# crossingsignals.net
KiCad netlist of a schematic drawn in EAGLE
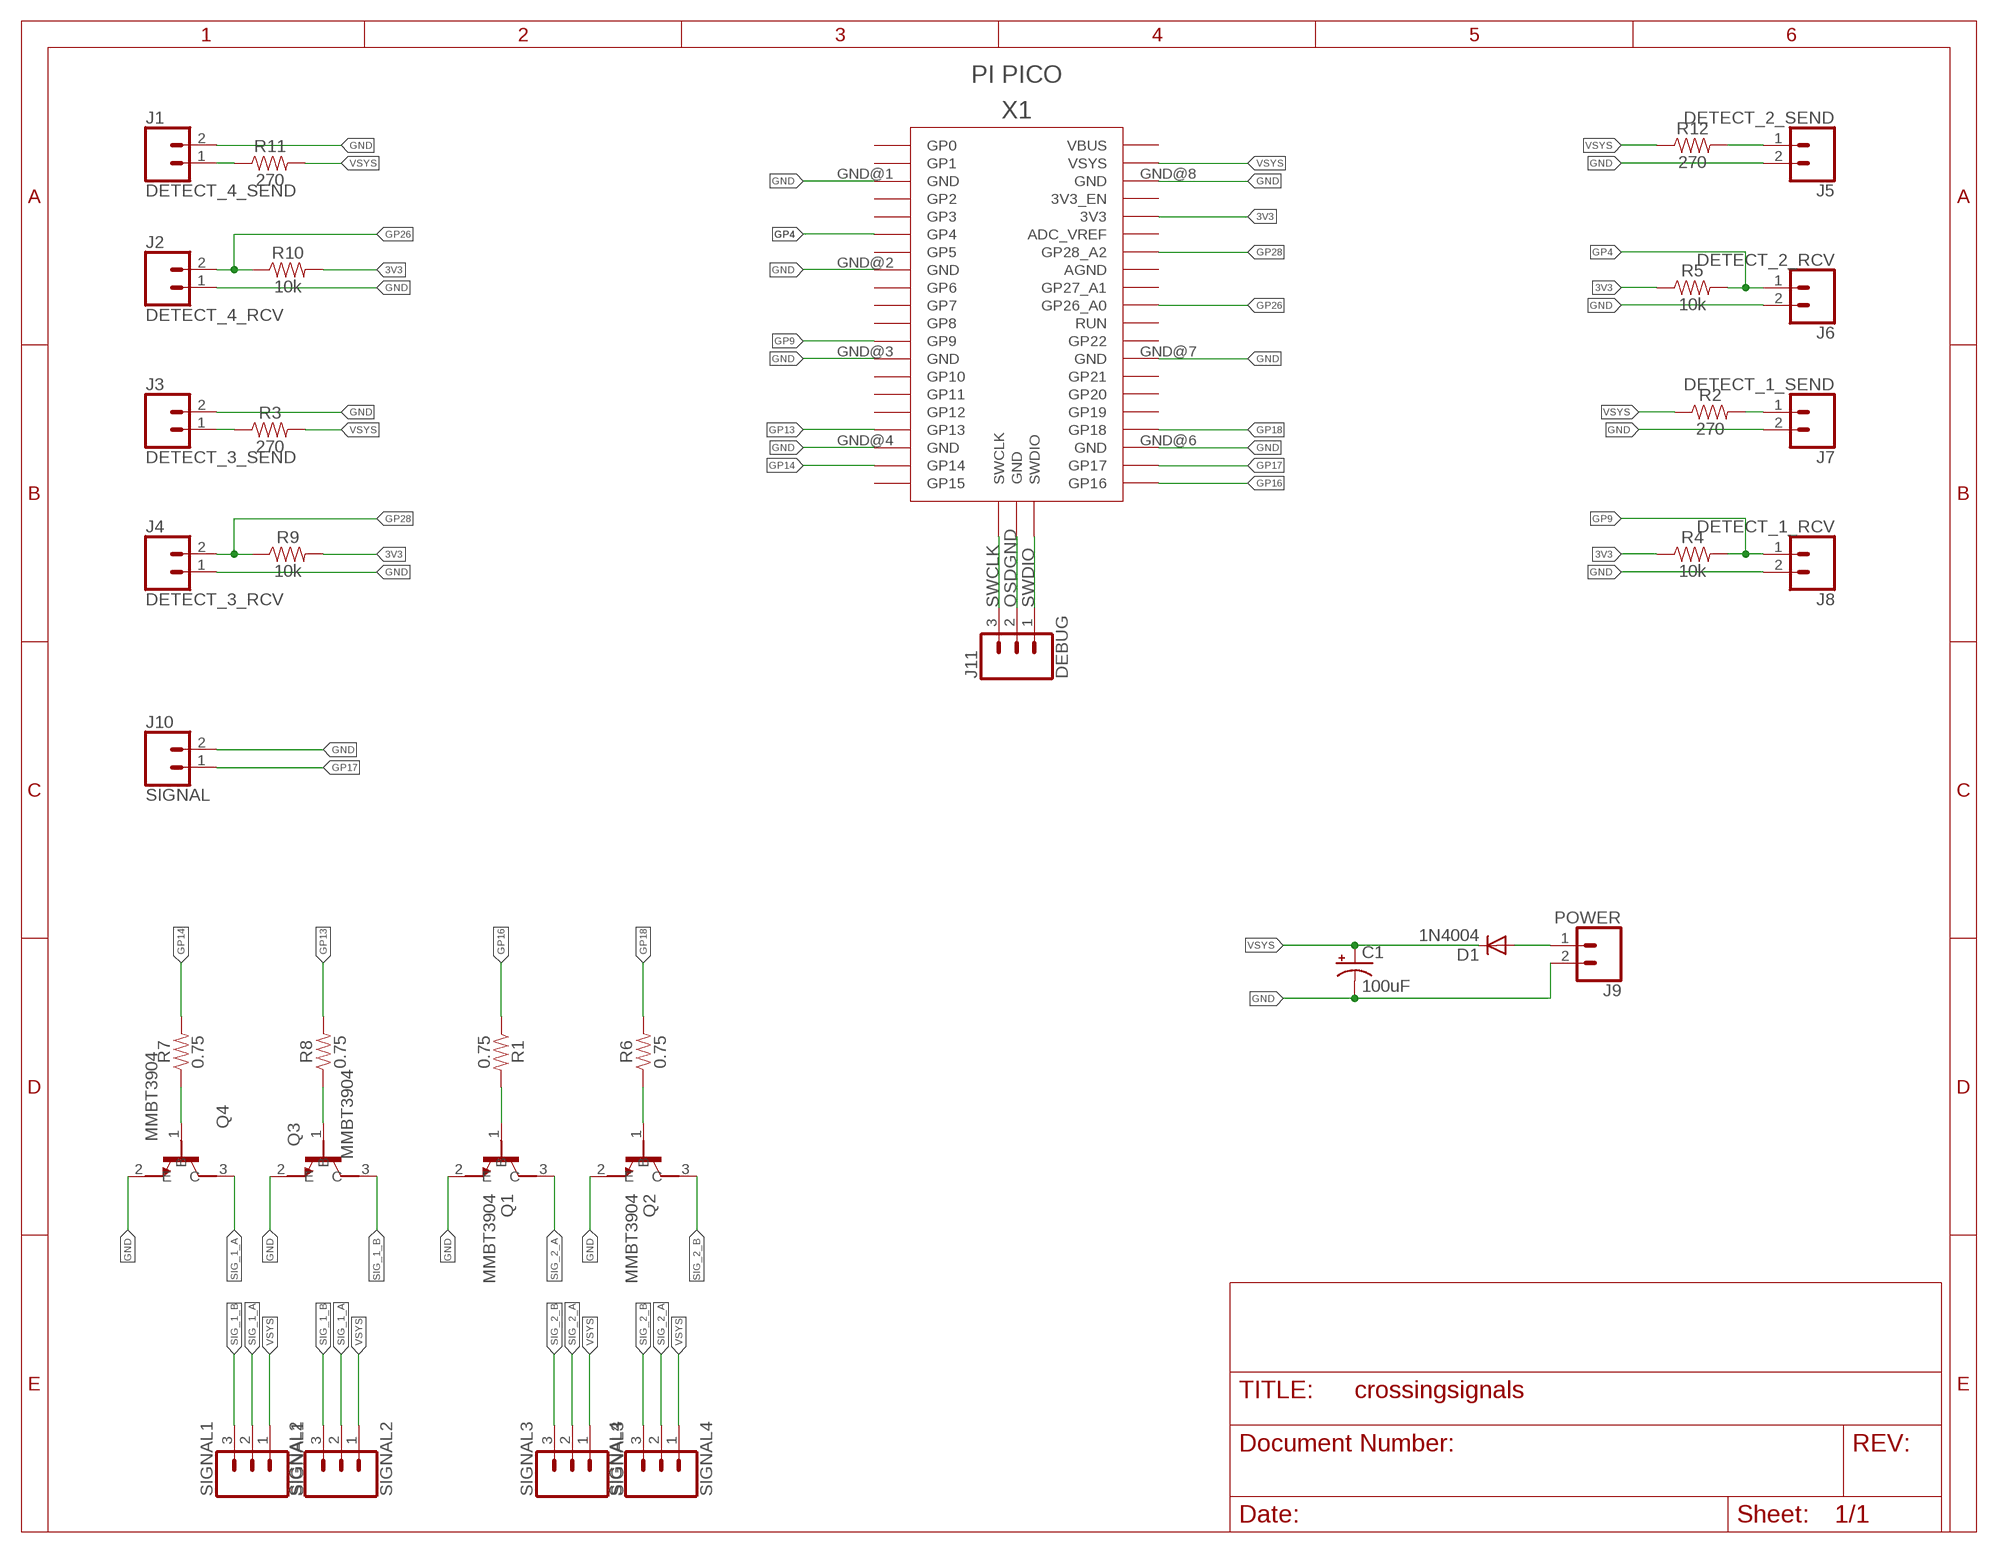
[diagram p0: schematic, sheet 1]

(export (version "E")
  (design (tool "Eeschema 10.0.6"))
  (components
    (comp (ref "C1")
      (value "100uF")
      (footprint "eagle-import:CPOL-RADIAL-2.5MM-6.5MM")
      (libsource (lib "eagle-import") (part "100UF-POLAR-RADIAL-2.5MM-25V-20%"))
    )
    (comp (ref "D1")
      (value "1N4004")
      (footprint "eagle-import:DO41-10")
      (libsource (lib "eagle-import") (part "1N4004"))
    )
    (comp (ref "J1")
      (value "DETECT_4_SEND")
      (footprint "eagle-import:1X02")
      (libsource (lib "eagle-import") (part "CONN_02"))
    )
    (comp (ref "J2")
      (value "DETECT_4_RCV")
      (footprint "eagle-import:1X02")
      (libsource (lib "eagle-import") (part "CONN_02"))
    )
    (comp (ref "J3")
      (value "DETECT_3_SEND")
      (footprint "eagle-import:1X02")
      (libsource (lib "eagle-import") (part "CONN_02"))
    )
    (comp (ref "J4")
      (value "DETECT_3_RCV")
      (footprint "eagle-import:1X02")
      (libsource (lib "eagle-import") (part "CONN_02"))
    )
    (comp (ref "J5")
      (value "DETECT_2_SEND")
      (footprint "eagle-import:1X02")
      (libsource (lib "eagle-import") (part "CONN_02"))
    )
    (comp (ref "J6")
      (value "DETECT_2_RCV")
      (footprint "eagle-import:1X02")
      (libsource (lib "eagle-import") (part "CONN_02"))
    )
    (comp (ref "J7")
      (value "DETECT_1_SEND")
      (footprint "eagle-import:1X02")
      (libsource (lib "eagle-import") (part "CONN_02"))
    )
    (comp (ref "J8")
      (value "DETECT_1_RCV")
      (footprint "eagle-import:1X02")
      (libsource (lib "eagle-import") (part "CONN_02"))
    )
    (comp (ref "J9")
      (value "POWER")
      (footprint "eagle-import:1X02")
      (libsource (lib "eagle-import") (part "CONN_02"))
    )
    (comp (ref "J10")
      (value "SIGNAL")
      (footprint "eagle-import:1X02")
      (libsource (lib "eagle-import") (part "CONN_02"))
    )
    (comp (ref "J11")
      (value "DEBUG")
      (footprint "eagle-import:1X03")
      (libsource (lib "eagle-import") (part "CONN_03"))
    )
    (comp (ref "Q1")
      (value "MMBT3904")
      (footprint "eagle-import:SOT95P240X120-3N")
      (fields (field (name "MF") "STMicroelectronics"))
      (libsource (lib "eagle-import") (part "MMBT3904"))
    )
    (comp (ref "Q2")
      (value "MMBT3904")
      (footprint "eagle-import:SOT95P240X120-3N")
      (fields (field (name "MF") "STMicroelectronics"))
      (libsource (lib "eagle-import") (part "MMBT3904"))
    )
    (comp (ref "Q3")
      (value "MMBT3904")
      (footprint "eagle-import:SOT95P240X120-3N")
      (fields (field (name "MF") "STMicroelectronics"))
      (libsource (lib "eagle-import") (part "MMBT3904"))
    )
    (comp (ref "Q4")
      (value "MMBT3904")
      (footprint "eagle-import:SOT95P240X120-3N")
      (fields (field (name "MF") "STMicroelectronics"))
      (libsource (lib "eagle-import") (part "MMBT3904"))
    )
    (comp (ref "R1")
      (value "0.75")
      (footprint "eagle-import:0805")
      (libsource (lib "eagle-import") (part "0.75OHM-0805-1/4W-1%"))
    )
    (comp (ref "R2")
      (value "270")
      (footprint "eagle-import:0805")
      (libsource (lib "eagle-import") (part "0.75OHM-0805-1/4W-1%"))
    )
    (comp (ref "R3")
      (value "270")
      (footprint "eagle-import:0805")
      (libsource (lib "eagle-import") (part "0.75OHM-0805-1/4W-1%"))
    )
    (comp (ref "R4")
      (value "10k")
      (footprint "eagle-import:0805")
      (libsource (lib "eagle-import") (part "0.75OHM-0805-1/4W-1%"))
    )
    (comp (ref "R5")
      (value "10k")
      (footprint "eagle-import:0805")
      (libsource (lib "eagle-import") (part "0.75OHM-0805-1/4W-1%"))
    )
    (comp (ref "R6")
      (value "0.75")
      (footprint "eagle-import:0805")
      (libsource (lib "eagle-import") (part "0.75OHM-0805-1/4W-1%"))
    )
    (comp (ref "R7")
      (value "0.75")
      (footprint "eagle-import:0805")
      (libsource (lib "eagle-import") (part "0.75OHM-0805-1/4W-1%"))
    )
    (comp (ref "R8")
      (value "0.75")
      (footprint "eagle-import:0805")
      (libsource (lib "eagle-import") (part "0.75OHM-0805-1/4W-1%"))
    )
    (comp (ref "R9")
      (value "10k")
      (footprint "eagle-import:0805")
      (libsource (lib "eagle-import") (part "0.75OHM-0805-1/4W-1%"))
    )
    (comp (ref "R10")
      (value "10k")
      (footprint "eagle-import:0805")
      (libsource (lib "eagle-import") (part "0.75OHM-0805-1/4W-1%"))
    )
    (comp (ref "R11")
      (value "270")
      (footprint "eagle-import:0805")
      (libsource (lib "eagle-import") (part "0.75OHM-0805-1/4W-1%"))
    )
    (comp (ref "R12")
      (value "270")
      (footprint "eagle-import:0805")
      (libsource (lib "eagle-import") (part "0.75OHM-0805-1/4W-1%"))
    )
    (comp (ref "SIGNAL1")
      (value "SIGNAL1")
      (footprint "eagle-import:1X03")
      (libsource (lib "eagle-import") (part "CONN_03"))
    )
    (comp (ref "SIGNAL2")
      (value "SIGNAL2")
      (footprint "eagle-import:1X03")
      (libsource (lib "eagle-import") (part "CONN_03"))
    )
    (comp (ref "SIGNAL3")
      (value "SIGNAL3")
      (footprint "eagle-import:1X03")
      (libsource (lib "eagle-import") (part "CONN_03"))
    )
    (comp (ref "SIGNAL4")
      (value "SIGNAL4")
      (footprint "eagle-import:1X03")
      (libsource (lib "eagle-import") (part "CONN_03"))
    )
    (comp (ref "X1")
      (value "PI PICO")
      (footprint "eagle-import:RPI_PICO_TH")
      (libsource (lib "eagle-import") (part "RPI_PICO_IG-TH"))
    )
  )
  (nets
    (net (code "1") (name "/OSDGND") (class "Default")
      (node (ref "J11") (pin "2") (pinfunction "2_2") (pintype "passive"))
      (node (ref "X1") (pin "GND@5") (pinfunction "GND_GND@5") (pintype "bidirectional"))
    )
    (net (code "2") (name "/SWCLK") (class "Default")
      (node (ref "J11") (pin "3") (pinfunction "3_3") (pintype "passive"))
      (node (ref "X1") (pin "SWCLK") (pinfunction "SWCLK_SWCLK") (pintype "bidirectional"))
    )
    (net (code "3") (name "/SWDIO") (class "Default")
      (node (ref "J11") (pin "1") (pinfunction "1_1") (pintype "passive"))
      (node (ref "X1") (pin "SWDIO") (pinfunction "SWDIO_SWDIO") (pintype "bidirectional"))
    )
    (net (code "4") (name "3V3") (class "Default")
      (node (ref "R10") (pin "2") (pinfunction "2_2") (pintype "passive"))
      (node (ref "R4") (pin "1") (pinfunction "1_1") (pintype "passive"))
      (node (ref "R5") (pin "1") (pinfunction "1_1") (pintype "passive"))
      (node (ref "R9") (pin "2") (pinfunction "2_2") (pintype "passive"))
      (node (ref "X1") (pin "3V3") (pinfunction "3V3_3V3") (pintype "bidirectional"))
    )
    (net (code "5") (name "GND") (class "Default")
      (node (ref "C1") (pin "2") (pinfunction "-_2") (pintype "passive"))
      (node (ref "J1") (pin "2") (pinfunction "2_2") (pintype "passive"))
      (node (ref "J10") (pin "2") (pinfunction "2_2") (pintype "passive"))
      (node (ref "J2") (pin "1") (pinfunction "1_1") (pintype "passive"))
      (node (ref "J3") (pin "2") (pinfunction "2_2") (pintype "passive"))
      (node (ref "J4") (pin "1") (pinfunction "1_1") (pintype "passive"))
      (node (ref "J5") (pin "2") (pinfunction "2_2") (pintype "passive"))
      (node (ref "J6") (pin "2") (pinfunction "2_2") (pintype "passive"))
      (node (ref "J7") (pin "2") (pinfunction "2_2") (pintype "passive"))
      (node (ref "J8") (pin "2") (pinfunction "2_2") (pintype "passive"))
      (node (ref "J9") (pin "2") (pinfunction "2_2") (pintype "passive"))
      (node (ref "Q1") (pin "2") (pinfunction "E_2") (pintype "passive"))
      (node (ref "Q2") (pin "2") (pinfunction "E_2") (pintype "passive"))
      (node (ref "Q3") (pin "2") (pinfunction "E_2") (pintype "passive"))
      (node (ref "Q4") (pin "2") (pinfunction "E_2") (pintype "passive"))
      (node (ref "X1") (pin "GND@1") (pinfunction "GND_GND@1") (pintype "bidirectional"))
      (node (ref "X1") (pin "GND@2") (pinfunction "GND_GND@2") (pintype "bidirectional"))
      (node (ref "X1") (pin "GND@3") (pinfunction "GND_GND@3") (pintype "bidirectional"))
      (node (ref "X1") (pin "GND@4") (pinfunction "GND_GND@4") (pintype "bidirectional"))
      (node (ref "X1") (pin "GND@6") (pinfunction "GND_GND@6") (pintype "bidirectional"))
      (node (ref "X1") (pin "GND@7") (pinfunction "GND_GND@7") (pintype "bidirectional"))
      (node (ref "X1") (pin "GND@8") (pinfunction "GND_GND@8") (pintype "bidirectional"))
    )
    (net (code "6") (name "GP4") (class "Default")
      (node (ref "J6") (pin "1") (pinfunction "1_1") (pintype "passive"))
      (node (ref "R5") (pin "2") (pinfunction "2_2") (pintype "passive"))
      (node (ref "X1") (pin "GP4") (pinfunction "GP4_GP4") (pintype "bidirectional"))
    )
    (net (code "7") (name "GP9") (class "Default")
      (node (ref "J8") (pin "1") (pinfunction "1_1") (pintype "passive"))
      (node (ref "R4") (pin "2") (pinfunction "2_2") (pintype "passive"))
      (node (ref "X1") (pin "GP9") (pinfunction "GP9_GP9") (pintype "bidirectional"))
    )
    (net (code "8") (name "GP13") (class "Default")
      (node (ref "R8") (pin "2") (pinfunction "2_2") (pintype "passive"))
      (node (ref "X1") (pin "GP13") (pinfunction "GP13_GP13") (pintype "bidirectional"))
    )
    (net (code "9") (name "GP14") (class "Default")
      (node (ref "R7") (pin "2") (pinfunction "2_2") (pintype "passive"))
      (node (ref "X1") (pin "GP14") (pinfunction "GP14_GP14") (pintype "bidirectional"))
    )
    (net (code "10") (name "GP16") (class "Default")
      (node (ref "R1") (pin "1") (pinfunction "1_1") (pintype "passive"))
      (node (ref "X1") (pin "GP16") (pinfunction "GP16_GP16") (pintype "bidirectional"))
    )
    (net (code "11") (name "GP17") (class "Default")
      (node (ref "J10") (pin "1") (pinfunction "1_1") (pintype "passive"))
      (node (ref "X1") (pin "GP17") (pinfunction "GP17_GP17") (pintype "bidirectional"))
    )
    (net (code "12") (name "GP18") (class "Default")
      (node (ref "R6") (pin "2") (pinfunction "2_2") (pintype "passive"))
      (node (ref "X1") (pin "GP18") (pinfunction "GP18_GP18") (pintype "bidirectional"))
    )
    (net (code "13") (name "GP26") (class "Default")
      (node (ref "J2") (pin "2") (pinfunction "2_2") (pintype "passive"))
      (node (ref "R10") (pin "1") (pinfunction "1_1") (pintype "passive"))
      (node (ref "X1") (pin "GP26_A0") (pinfunction "GP26_A0_GP26_A0") (pintype "bidirectional"))
    )
    (net (code "14") (name "GP28") (class "Default")
      (node (ref "J4") (pin "2") (pinfunction "2_2") (pintype "passive"))
      (node (ref "R9") (pin "1") (pinfunction "1_1") (pintype "passive"))
      (node (ref "X1") (pin "GP28_A2") (pinfunction "GP28_A2_GP28_A2") (pintype "bidirectional"))
    )
    (net (code "15") (name "Net-(D1-PadA)") (class "Default")
      (node (ref "D1") (pin "A") (pinfunction "A_A") (pintype "passive"))
      (node (ref "J9") (pin "1") (pinfunction "1_1") (pintype "passive"))
    )
    (net (code "16") (name "Net-(J1-Pad1)") (class "Default")
      (node (ref "J1") (pin "1") (pinfunction "1_1") (pintype "passive"))
      (node (ref "R11") (pin "1") (pinfunction "1_1") (pintype "passive"))
    )
    (net (code "17") (name "Net-(J3-Pad1)") (class "Default")
      (node (ref "J3") (pin "1") (pinfunction "1_1") (pintype "passive"))
      (node (ref "R3") (pin "1") (pinfunction "1_1") (pintype "passive"))
    )
    (net (code "18") (name "Net-(J5-Pad1)") (class "Default")
      (node (ref "J5") (pin "1") (pinfunction "1_1") (pintype "passive"))
      (node (ref "R12") (pin "2") (pinfunction "2_2") (pintype "passive"))
    )
    (net (code "19") (name "Net-(J7-Pad1)") (class "Default")
      (node (ref "J7") (pin "1") (pinfunction "1_1") (pintype "passive"))
      (node (ref "R2") (pin "2") (pinfunction "2_2") (pintype "passive"))
    )
    (net (code "20") (name "Net-(Q1-B)") (class "Default")
      (node (ref "Q1") (pin "1") (pinfunction "B_1") (pintype "passive"))
      (node (ref "R1") (pin "2") (pinfunction "2_2") (pintype "passive"))
    )
    (net (code "21") (name "Net-(Q2-B)") (class "Default")
      (node (ref "Q2") (pin "1") (pinfunction "B_1") (pintype "passive"))
      (node (ref "R6") (pin "1") (pinfunction "1_1") (pintype "passive"))
    )
    (net (code "22") (name "Net-(Q3-B)") (class "Default")
      (node (ref "Q3") (pin "1") (pinfunction "B_1") (pintype "passive"))
      (node (ref "R8") (pin "1") (pinfunction "1_1") (pintype "passive"))
    )
    (net (code "23") (name "Net-(Q4-B)") (class "Default")
      (node (ref "Q4") (pin "1") (pinfunction "B_1") (pintype "passive"))
      (node (ref "R7") (pin "1") (pinfunction "1_1") (pintype "passive"))
    )
    (net (code "24") (name "SIG_1_A") (class "Default")
      (node (ref "Q4") (pin "3") (pinfunction "C_3") (pintype "passive"))
      (node (ref "SIGNAL1") (pin "2") (pinfunction "2_2") (pintype "passive"))
      (node (ref "SIGNAL2") (pin "2") (pinfunction "2_2") (pintype "passive"))
    )
    (net (code "25") (name "SIG_1_B") (class "Default")
      (node (ref "Q3") (pin "3") (pinfunction "C_3") (pintype "passive"))
      (node (ref "SIGNAL1") (pin "3") (pinfunction "3_3") (pintype "passive"))
      (node (ref "SIGNAL2") (pin "3") (pinfunction "3_3") (pintype "passive"))
    )
    (net (code "26") (name "SIG_2_A") (class "Default")
      (node (ref "Q1") (pin "3") (pinfunction "C_3") (pintype "passive"))
      (node (ref "SIGNAL3") (pin "2") (pinfunction "2_2") (pintype "passive"))
      (node (ref "SIGNAL4") (pin "2") (pinfunction "2_2") (pintype "passive"))
    )
    (net (code "27") (name "SIG_2_B") (class "Default")
      (node (ref "Q2") (pin "3") (pinfunction "C_3") (pintype "passive"))
      (node (ref "SIGNAL3") (pin "3") (pinfunction "3_3") (pintype "passive"))
      (node (ref "SIGNAL4") (pin "3") (pinfunction "3_3") (pintype "passive"))
    )
    (net (code "28") (name "VSYS") (class "Default")
      (node (ref "C1") (pin "1") (pinfunction "+_1") (pintype "passive"))
      (node (ref "D1") (pin "C") (pinfunction "C_C") (pintype "passive"))
      (node (ref "R11") (pin "2") (pinfunction "2_2") (pintype "passive"))
      (node (ref "R12") (pin "1") (pinfunction "1_1") (pintype "passive"))
      (node (ref "R2") (pin "1") (pinfunction "1_1") (pintype "passive"))
      (node (ref "R3") (pin "2") (pinfunction "2_2") (pintype "passive"))
      (node (ref "SIGNAL1") (pin "1") (pinfunction "1_1") (pintype "passive"))
      (node (ref "SIGNAL2") (pin "1") (pinfunction "1_1") (pintype "passive"))
      (node (ref "SIGNAL3") (pin "1") (pinfunction "1_1") (pintype "passive"))
      (node (ref "SIGNAL4") (pin "1") (pinfunction "1_1") (pintype "passive"))
      (node (ref "X1") (pin "VSYS") (pinfunction "VSYS_VSYS") (pintype "bidirectional"))
    )
    (net (code "29") (name "unconnected-(X1-Pad3V3_EN)") (class "Default")
      (node (ref "X1") (pin "3V3_EN") (pinfunction "3V3_EN_3V3_EN") (pintype "bidirectional"))
    )
    (net (code "30") (name "unconnected-(X1-PadADC_VREF)") (class "Default")
      (node (ref "X1") (pin "ADC_VREF") (pinfunction "ADC_VREF_ADC_VREF") (pintype "bidirectional"))
    )
    (net (code "31") (name "unconnected-(X1-PadAGND)") (class "Default")
      (node (ref "X1") (pin "AGND") (pinfunction "AGND_AGND") (pintype "bidirectional"))
    )
    (net (code "32") (name "unconnected-(X1-PadGP0)") (class "Default")
      (node (ref "X1") (pin "GP0") (pinfunction "GP0_GP0") (pintype "bidirectional"))
    )
    (net (code "33") (name "unconnected-(X1-PadGP1)") (class "Default")
      (node (ref "X1") (pin "GP1") (pinfunction "GP1_GP1") (pintype "bidirectional"))
    )
    (net (code "34") (name "unconnected-(X1-PadGP2)") (class "Default")
      (node (ref "X1") (pin "GP2") (pinfunction "GP2_GP2") (pintype "bidirectional"))
    )
    (net (code "35") (name "unconnected-(X1-PadGP3)") (class "Default")
      (node (ref "X1") (pin "GP3") (pinfunction "GP3_GP3") (pintype "bidirectional"))
    )
    (net (code "36") (name "unconnected-(X1-PadGP5)") (class "Default")
      (node (ref "X1") (pin "GP5") (pinfunction "GP5_GP5") (pintype "bidirectional"))
    )
    (net (code "37") (name "unconnected-(X1-PadGP6)") (class "Default")
      (node (ref "X1") (pin "GP6") (pinfunction "GP6_GP6") (pintype "bidirectional"))
    )
    (net (code "38") (name "unconnected-(X1-PadGP7)") (class "Default")
      (node (ref "X1") (pin "GP7") (pinfunction "GP7_GP7") (pintype "bidirectional"))
    )
    (net (code "39") (name "unconnected-(X1-PadGP8)") (class "Default")
      (node (ref "X1") (pin "GP8") (pinfunction "GP8_GP8") (pintype "bidirectional"))
    )
    (net (code "40") (name "unconnected-(X1-PadGP10)") (class "Default")
      (node (ref "X1") (pin "GP10") (pinfunction "GP10_GP10") (pintype "bidirectional"))
    )
    (net (code "41") (name "unconnected-(X1-PadGP11)") (class "Default")
      (node (ref "X1") (pin "GP11") (pinfunction "GP11_GP11") (pintype "bidirectional"))
    )
    (net (code "42") (name "unconnected-(X1-PadGP12)") (class "Default")
      (node (ref "X1") (pin "GP12") (pinfunction "GP12_GP12") (pintype "bidirectional"))
    )
    (net (code "43") (name "unconnected-(X1-PadGP15)") (class "Default")
      (node (ref "X1") (pin "GP15") (pinfunction "GP15_GP15") (pintype "bidirectional"))
    )
    (net (code "44") (name "unconnected-(X1-PadGP19)") (class "Default")
      (node (ref "X1") (pin "GP19") (pinfunction "GP19_GP19") (pintype "bidirectional"))
    )
    (net (code "45") (name "unconnected-(X1-PadGP20)") (class "Default")
      (node (ref "X1") (pin "GP20") (pinfunction "GP20_GP20") (pintype "bidirectional"))
    )
    (net (code "46") (name "unconnected-(X1-PadGP21)") (class "Default")
      (node (ref "X1") (pin "GP21") (pinfunction "GP21_GP21") (pintype "bidirectional"))
    )
    (net (code "47") (name "unconnected-(X1-PadGP22)") (class "Default")
      (node (ref "X1") (pin "GP22") (pinfunction "GP22_GP22") (pintype "bidirectional"))
    )
    (net (code "48") (name "unconnected-(X1-PadGP27_A1)") (class "Default")
      (node (ref "X1") (pin "GP27_A1") (pinfunction "GP27_A1_GP27_A1") (pintype "bidirectional"))
    )
    (net (code "49") (name "unconnected-(X1-PadRUN)") (class "Default")
      (node (ref "X1") (pin "RUN") (pinfunction "RUN_RUN") (pintype "bidirectional"))
    )
    (net (code "50") (name "unconnected-(X1-PadVBUS)") (class "Default")
      (node (ref "X1") (pin "VBUS") (pinfunction "VBUS_VBUS") (pintype "bidirectional"))
    )
  )
)
